# OSSC_HDMI_Audio_v1_5_A3b.net
KiCad netlist of a schematic drawn in EAGLE
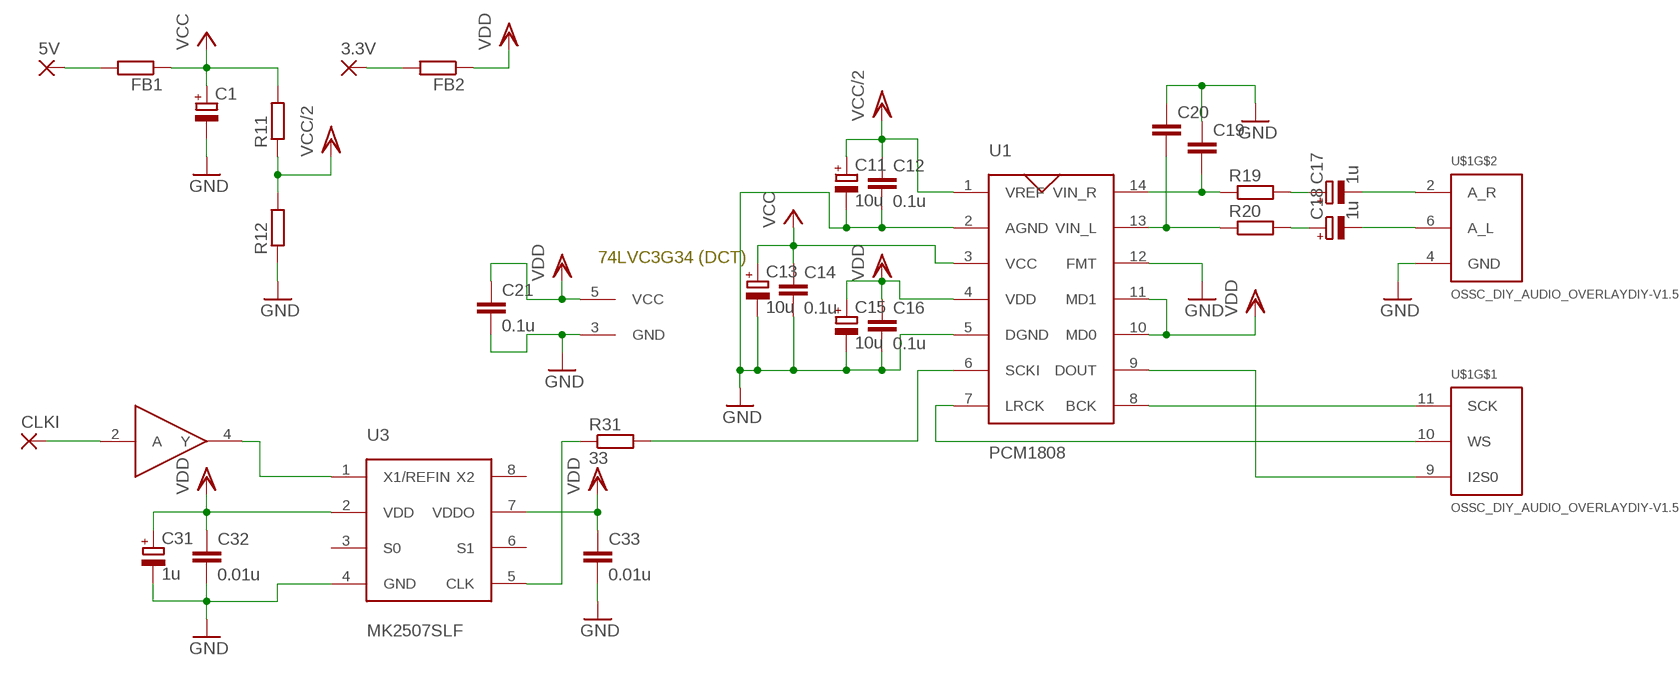
[diagram p0: schematic, sheet 1]

(export (version "E")
  (design (tool "Eeschema 10.0.6"))
  (components
    (comp (ref "3.3V")
      (value "SMD2")
      (footprint "eagle-import:SMD1,27-2,54")
      (libsource (lib "eagle-import") (part "SMD2"))
    )
    (comp (ref "5V")
      (value "SMD2")
      (footprint "eagle-import:SMD1,27-2,54")
      (libsource (lib "eagle-import") (part "SMD2"))
    )
    (comp (ref "C1")
      (value "CPOL-EUSMCC")
      (footprint "eagle-import:SMC_C")
      (libsource (lib "eagle-import") (part "CPOL-EUSMCC"))
    )
    (comp (ref "C11")
      (value "10u")
      (footprint "eagle-import:SMC_A")
      (libsource (lib "eagle-import") (part "CPOL-EUSMCA"))
    )
    (comp (ref "C12")
      (value "0.1u")
      (footprint "eagle-import:C0603")
      (libsource (lib "eagle-import") (part "C-EUC0603"))
    )
    (comp (ref "C13")
      (value "10u")
      (footprint "eagle-import:SMC_A")
      (libsource (lib "eagle-import") (part "CPOL-EUSMCA"))
    )
    (comp (ref "C14")
      (value "0.1u")
      (footprint "eagle-import:C0603")
      (libsource (lib "eagle-import") (part "C-EUC0603"))
    )
    (comp (ref "C15")
      (value "10u")
      (footprint "eagle-import:SMC_A")
      (libsource (lib "eagle-import") (part "CPOL-EUSMCA"))
    )
    (comp (ref "C16")
      (value "0.1u")
      (footprint "eagle-import:C0603")
      (libsource (lib "eagle-import") (part "C-EUC0603"))
    )
    (comp (ref "C17")
      (value "1u")
      (footprint "eagle-import:SMC_A")
      (libsource (lib "eagle-import") (part "CPOL-EUSMCA"))
    )
    (comp (ref "C18")
      (value "1u")
      (footprint "eagle-import:SMC_A")
      (libsource (lib "eagle-import") (part "CPOL-EUSMCA"))
    )
    (comp (ref "C19")
      (value "C-EUC0603")
      (footprint "eagle-import:C0603")
      (libsource (lib "eagle-import") (part "C-EUC0603"))
    )
    (comp (ref "C20")
      (value "C-EUC0603")
      (footprint "eagle-import:C0603")
      (libsource (lib "eagle-import") (part "C-EUC0603"))
    )
    (comp (ref "C21")
      (value "0.1u")
      (footprint "eagle-import:C0603")
      (libsource (lib "eagle-import") (part "C-EUC0603"))
    )
    (comp (ref "C31")
      (value "1u")
      (footprint "eagle-import:SMC_A")
      (libsource (lib "eagle-import") (part "CPOL-EUSMCA"))
    )
    (comp (ref "C32")
      (value "0.01u")
      (footprint "eagle-import:C0603")
      (libsource (lib "eagle-import") (part "C-EUC0603"))
    )
    (comp (ref "C33")
      (value "0.01u")
      (footprint "eagle-import:C0603")
      (libsource (lib "eagle-import") (part "C-EUC0603"))
    )
    (comp (ref "CLKI")
      (value "SMD2")
      (footprint "eagle-import:SMD1,27-2,54")
      (libsource (lib "eagle-import") (part "SMD2"))
    )
    (comp (ref "FB1")
      (value "R-EU_R0603")
      (footprint "eagle-import:R0603")
      (libsource (lib "eagle-import") (part "R-EU_R0603"))
    )
    (comp (ref "FB2")
      (value "R-EU_R0603")
      (footprint "eagle-import:R0603")
      (libsource (lib "eagle-import") (part "R-EU_R0603"))
    )
    (comp (ref "R11")
      (value "R-EU_R0603")
      (footprint "eagle-import:R0603")
      (libsource (lib "eagle-import") (part "R-EU_R0603"))
    )
    (comp (ref "R12")
      (value "R-EU_R0603")
      (footprint "eagle-import:R0603")
      (libsource (lib "eagle-import") (part "R-EU_R0603"))
    )
    (comp (ref "R19")
      (value "R-EU_R0603")
      (footprint "eagle-import:R0603")
      (libsource (lib "eagle-import") (part "R-EU_R0603"))
    )
    (comp (ref "R20")
      (value "R-EU_R0603")
      (footprint "eagle-import:R0603")
      (libsource (lib "eagle-import") (part "R-EU_R0603"))
    )
    (comp (ref "R31")
      (value "33")
      (footprint "eagle-import:R0603")
      (libsource (lib "eagle-import") (part "R-EU_R0603"))
    )
    (comp (ref "U$1")
      (value "OSSC_DIY_AUDIO_OVERLAYDIY-V1.5")
      (footprint "eagle-import:OSSC_OVERLAY_V1.5")
      (libsource (lib "eagle-import") (part "OSSC_DIY_AUDIO_OVERLAYDIY-V1.5"))
    )
    (comp (ref "U1")
      (value "PCM1808")
      (footprint "eagle-import:PCM1808")
      (libsource (lib "eagle-import") (part "PCM1808"))
    )
    (comp (ref "U2")
      (value "74LVC1G34")
      (footprint "eagle-import:74LVC1G34DCK")
      (libsource (lib "eagle-import") (part "74LVC1G34"))
    )
    (comp (ref "U3")
      (value "MK2507SLF")
      (footprint "eagle-import:SOIC8")
      (libsource (lib "eagle-import") (part "MK2507SLF"))
    )
  )
  (nets
    (net (code "1") (name "GND") (class "Default")
      (node (ref "C1") (pin "-") (pinfunction "-_-") (pintype "passive"))
      (node (ref "C11") (pin "-") (pinfunction "-_-") (pintype "passive"))
      (node (ref "C12") (pin "2") (pinfunction "2_2") (pintype "passive"))
      (node (ref "C13") (pin "-") (pinfunction "-_-") (pintype "passive"))
      (node (ref "C14") (pin "2") (pinfunction "2_2") (pintype "passive"))
      (node (ref "C15") (pin "-") (pinfunction "-_-") (pintype "passive"))
      (node (ref "C16") (pin "2") (pinfunction "2_2") (pintype "passive"))
      (node (ref "C19") (pin "1") (pinfunction "1_1") (pintype "passive"))
      (node (ref "C20") (pin "1") (pinfunction "1_1") (pintype "passive"))
      (node (ref "C21") (pin "2") (pinfunction "2_2") (pintype "passive"))
      (node (ref "C31") (pin "-") (pinfunction "-_-") (pintype "passive"))
      (node (ref "C32") (pin "2") (pinfunction "2_2") (pintype "passive"))
      (node (ref "C33") (pin "2") (pinfunction "2_2") (pintype "passive"))
      (node (ref "R12") (pin "1") (pinfunction "1_1") (pintype "passive"))
      (node (ref "U$1") (pin "4") (pinfunction "GND_4") (pintype "bidirectional"))
      (node (ref "U1") (pin "12") (pinfunction "FMT_12") (pintype "bidirectional"))
      (node (ref "U1") (pin "2") (pinfunction "AGND_2") (pintype "bidirectional"))
      (node (ref "U1") (pin "5") (pinfunction "DGND_5") (pintype "bidirectional"))
      (node (ref "U2") (pin "3") (pinfunction "GND_3") (pintype "bidirectional"))
      (node (ref "U3") (pin "4") (pinfunction "GND_4") (pintype "bidirectional"))
    )
    (net (code "2") (name "Net-(3.3V-P)") (class "Default")
      (node (ref "3.3V") (pin "1") (pinfunction "P_1") (pintype "passive"))
      (node (ref "FB2") (pin "2") (pinfunction "2_2") (pintype "passive"))
    )
    (net (code "3") (name "Net-(5V-P)") (class "Default")
      (node (ref "5V") (pin "1") (pinfunction "P_1") (pintype "passive"))
      (node (ref "FB1") (pin "2") (pinfunction "2_2") (pintype "passive"))
    )
    (net (code "4") (name "Net-(C17-Pad+)") (class "Default")
      (node (ref "C17") (pin "+") (pinfunction "+_+") (pintype "passive"))
      (node (ref "R19") (pin "2") (pinfunction "2_2") (pintype "passive"))
    )
    (net (code "5") (name "Net-(C18-Pad+)") (class "Default")
      (node (ref "C18") (pin "+") (pinfunction "+_+") (pintype "passive"))
      (node (ref "R20") (pin "2") (pinfunction "2_2") (pintype "passive"))
    )
    (net (code "6") (name "Net-(CLKI-P)") (class "Default")
      (node (ref "CLKI") (pin "1") (pinfunction "P_1") (pintype "passive"))
      (node (ref "U2") (pin "2") (pinfunction "A_2") (pintype "bidirectional"))
    )
    (net (code "7") (name "Net-(U$1A-I2S0)") (class "Default")
      (node (ref "U$1") (pin "9") (pinfunction "I2S0_9") (pintype "bidirectional"))
      (node (ref "U1") (pin "9") (pinfunction "DOUT_9") (pintype "bidirectional"))
    )
    (net (code "8") (name "Net-(U$1A-SCK)") (class "Default")
      (node (ref "U$1") (pin "11") (pinfunction "SCK_11") (pintype "bidirectional"))
      (node (ref "U1") (pin "8") (pinfunction "BCK_8") (pintype "bidirectional"))
    )
    (net (code "9") (name "Net-(U$1A-WS)") (class "Default")
      (node (ref "U$1") (pin "10") (pinfunction "WS_10") (pintype "bidirectional"))
      (node (ref "U1") (pin "7") (pinfunction "LRCK_7") (pintype "bidirectional"))
    )
    (net (code "10") (name "Net-(U$1B-A_L)") (class "Default")
      (node (ref "C18") (pin "-") (pinfunction "-_-") (pintype "passive"))
      (node (ref "U$1") (pin "6") (pinfunction "A_L_6") (pintype "bidirectional"))
    )
    (net (code "11") (name "Net-(U$1B-A_R)") (class "Default")
      (node (ref "C17") (pin "-") (pinfunction "-_-") (pintype "passive"))
      (node (ref "U$1") (pin "2") (pinfunction "A_R_2") (pintype "bidirectional"))
    )
    (net (code "12") (name "Net-(U1-SCKI)") (class "Default")
      (node (ref "R31") (pin "2") (pinfunction "2_2") (pintype "passive"))
      (node (ref "U1") (pin "6") (pinfunction "SCKI_6") (pintype "bidirectional"))
    )
    (net (code "13") (name "Net-(U1-VIN_L)") (class "Default")
      (node (ref "C20") (pin "2") (pinfunction "2_2") (pintype "passive"))
      (node (ref "R20") (pin "1") (pinfunction "1_1") (pintype "passive"))
      (node (ref "U1") (pin "13") (pinfunction "VIN_L_13") (pintype "bidirectional"))
    )
    (net (code "14") (name "Net-(U1-VIN_R)") (class "Default")
      (node (ref "C19") (pin "2") (pinfunction "2_2") (pintype "passive"))
      (node (ref "R19") (pin "1") (pinfunction "1_1") (pintype "passive"))
      (node (ref "U1") (pin "14") (pinfunction "VIN_R_14") (pintype "bidirectional"))
    )
    (net (code "15") (name "Net-(U2A-Y)") (class "Default")
      (node (ref "U2") (pin "4") (pinfunction "Y_4") (pintype "bidirectional"))
      (node (ref "U3") (pin "1") (pinfunction "X1/REFIN_1") (pintype "bidirectional"))
    )
    (net (code "16") (name "Net-(U3-CLK)") (class "Default")
      (node (ref "R31") (pin "1") (pinfunction "1_1") (pintype "passive"))
      (node (ref "U3") (pin "5") (pinfunction "CLK_5") (pintype "bidirectional"))
    )
    (net (code "17") (name "VCC") (class "Default")
      (node (ref "C1") (pin "+") (pinfunction "+_+") (pintype "passive"))
      (node (ref "C13") (pin "+") (pinfunction "+_+") (pintype "passive"))
      (node (ref "C14") (pin "1") (pinfunction "1_1") (pintype "passive"))
      (node (ref "FB1") (pin "1") (pinfunction "1_1") (pintype "passive"))
      (node (ref "R11") (pin "2") (pinfunction "2_2") (pintype "passive"))
      (node (ref "U1") (pin "3") (pinfunction "VCC_3") (pintype "bidirectional"))
    )
    (net (code "18") (name "VCC{slash}2") (class "Default")
      (node (ref "C11") (pin "+") (pinfunction "+_+") (pintype "passive"))
      (node (ref "C12") (pin "1") (pinfunction "1_1") (pintype "passive"))
      (node (ref "R11") (pin "1") (pinfunction "1_1") (pintype "passive"))
      (node (ref "R12") (pin "2") (pinfunction "2_2") (pintype "passive"))
      (node (ref "U1") (pin "1") (pinfunction "VREF_1") (pintype "bidirectional"))
    )
    (net (code "19") (name "VDD") (class "Default")
      (node (ref "C15") (pin "+") (pinfunction "+_+") (pintype "passive"))
      (node (ref "C16") (pin "1") (pinfunction "1_1") (pintype "passive"))
      (node (ref "C21") (pin "1") (pinfunction "1_1") (pintype "passive"))
      (node (ref "C31") (pin "+") (pinfunction "+_+") (pintype "passive"))
      (node (ref "C32") (pin "1") (pinfunction "1_1") (pintype "passive"))
      (node (ref "C33") (pin "1") (pinfunction "1_1") (pintype "passive"))
      (node (ref "FB2") (pin "1") (pinfunction "1_1") (pintype "passive"))
      (node (ref "U1") (pin "10") (pinfunction "MD0_10") (pintype "bidirectional"))
      (node (ref "U1") (pin "11") (pinfunction "MD1_11") (pintype "bidirectional"))
      (node (ref "U1") (pin "4") (pinfunction "VDD_4") (pintype "bidirectional"))
      (node (ref "U2") (pin "5") (pinfunction "VCC_5") (pintype "bidirectional"))
      (node (ref "U3") (pin "2") (pinfunction "VDD_2") (pintype "bidirectional"))
      (node (ref "U3") (pin "7") (pinfunction "VDDO_7") (pintype "bidirectional"))
    )
    (net (code "20") (name "unconnected-(U3-S0-Pad3)") (class "Default")
      (node (ref "U3") (pin "3") (pinfunction "S0_3") (pintype "bidirectional"))
    )
    (net (code "21") (name "unconnected-(U3-S1-Pad6)") (class "Default")
      (node (ref "U3") (pin "6") (pinfunction "S1_6") (pintype "bidirectional"))
    )
    (net (code "22") (name "unconnected-(U3-X2-Pad8)") (class "Default")
      (node (ref "U3") (pin "8") (pinfunction "X2_8") (pintype "bidirectional"))
    )
  )
)
